# Tiras_LED.net
KiCad netlist of a schematic drawn in Altium Designer
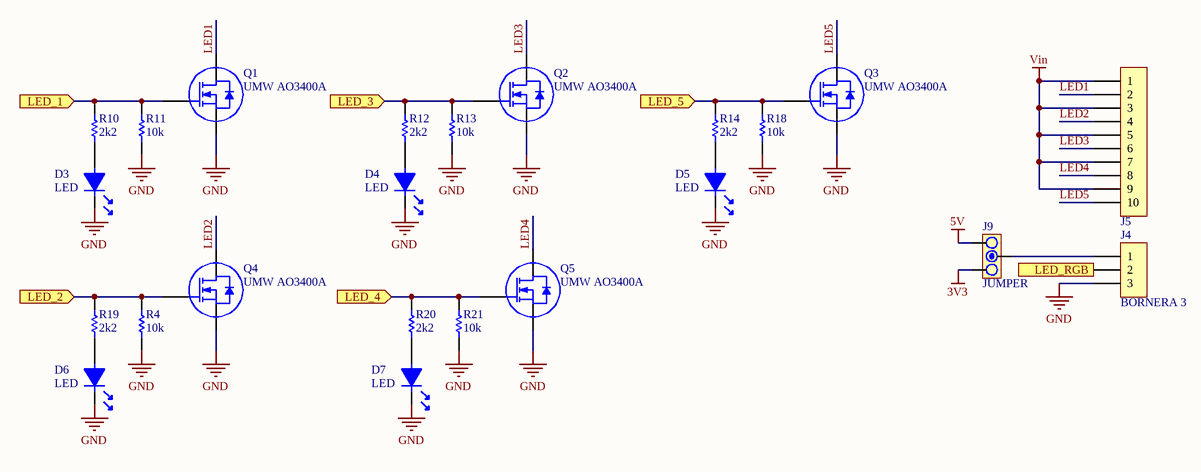
[diagram p0: Tiras LED.SchDoc]

(export (version "E")
  (design (tool "Eeschema 10.0.6"))
  (components
    (comp (ref "D3") (value "LED") (footprint "LED0805") (libsource (lib "LIBPIOIX") (part "LED")))
    (comp (ref "D4") (value "LED") (footprint "LED0805") (libsource (lib "LIBPIOIX") (part "LED")))
    (comp (ref "D5") (value "LED") (footprint "LED0805") (libsource (lib "LIBPIOIX") (part "LED")))
    (comp (ref "D6") (value "LED") (footprint "LED0805") (libsource (lib "LIBPIOIX") (part "LED")))
    (comp (ref "D7") (value "LED") (footprint "LED0805") (libsource (lib "LIBPIOIX") (part "LED")))
    (comp (ref "J4")
      (value "BORNERA 3")
      (footprint "BORNERA3")
      (libsource (lib "LIBPIOIX") (part "BORNERA 3"))
    )
    (comp (ref "J5")
      (value "BORNERA10")
      (footprint "BORNERA10")
      (libsource (lib "LIBPIOIX") (part "BORNERA10"))
    )
    (comp (ref "J9") (value "JUMPER") (footprint "JUMPER3") (libsource (lib "LIBPIOIX") (part "JUMPER3")))
    (comp (ref "Q1") (value "UMW AO3400A") (footprint "SOT23") (libsource (lib "LIBPIOIX") (part "MOSFET N")))
    (comp (ref "Q2") (value "UMW AO3400A") (footprint "SOT23") (libsource (lib "LIBPIOIX") (part "MOSFET N")))
    (comp (ref "Q3") (value "UMW AO3400A") (footprint "SOT23") (libsource (lib "LIBPIOIX") (part "MOSFET N")))
    (comp (ref "Q4") (value "UMW AO3400A") (footprint "SOT23") (libsource (lib "LIBPIOIX") (part "MOSFET N")))
    (comp (ref "Q5") (value "UMW AO3400A") (footprint "SOT23") (libsource (lib "LIBPIOIX") (part "MOSFET N")))
    (comp (ref "R4") (value "10k") (footprint "0805") (libsource (lib "LIBPIOIX") (part "RES")))
    (comp (ref "R10") (value "2k2") (footprint "0805") (libsource (lib "LIBPIOIX") (part "RES")))
    (comp (ref "R11") (value "10k") (footprint "0805") (libsource (lib "LIBPIOIX") (part "RES")))
    (comp (ref "R12") (value "2k2") (footprint "0805") (libsource (lib "LIBPIOIX") (part "RES")))
    (comp (ref "R13") (value "10k") (footprint "0805") (libsource (lib "LIBPIOIX") (part "RES")))
    (comp (ref "R14") (value "2k2") (footprint "0805") (libsource (lib "LIBPIOIX") (part "RES")))
    (comp (ref "R18") (value "10k") (footprint "0805") (libsource (lib "LIBPIOIX") (part "RES")))
    (comp (ref "R19") (value "2k2") (footprint "0805") (libsource (lib "LIBPIOIX") (part "RES")))
    (comp (ref "R20") (value "2k2") (footprint "0805") (libsource (lib "LIBPIOIX") (part "RES")))
    (comp (ref "R21") (value "10k") (footprint "0805") (libsource (lib "LIBPIOIX") (part "RES")))
  )
  (nets
    (net (code "1") (name "/LED1") (class "Default")
      (node (ref "J5") (pin "2") (pinfunction "2_2") (pintype "passive"))
      (node (ref "Q1") (pin "2") (pinfunction "D_2") (pintype "passive"))
    )
    (net (code "2") (name "/LED2") (class "Default")
      (node (ref "J5") (pin "4") (pinfunction "4_4") (pintype "passive"))
      (node (ref "Q4") (pin "2") (pinfunction "D_2") (pintype "passive"))
    )
    (net (code "3") (name "/LED3") (class "Default")
      (node (ref "J5") (pin "6") (pinfunction "6_6") (pintype "passive"))
      (node (ref "Q2") (pin "2") (pinfunction "D_2") (pintype "passive"))
    )
    (net (code "4") (name "/LED4") (class "Default")
      (node (ref "J5") (pin "8") (pinfunction "8_8") (pintype "passive"))
      (node (ref "Q5") (pin "2") (pinfunction "D_2") (pintype "passive"))
    )
    (net (code "5") (name "/LED5") (class "Default")
      (node (ref "J5") (pin "10") (pinfunction "10_10") (pintype "passive"))
      (node (ref "Q3") (pin "2") (pinfunction "D_2") (pintype "passive"))
    )
    (net (code "6") (name "/LED_1") (class "Default")
      (node (ref "Q1") (pin "1") (pinfunction "G_1") (pintype "passive"))
      (node (ref "R10") (pin "2") (pinfunction "2_2") (pintype "passive"))
      (node (ref "R11") (pin "2") (pinfunction "2_2") (pintype "passive"))
    )
    (net (code "7") (name "/LED_2") (class "Default")
      (node (ref "Q4") (pin "1") (pinfunction "G_1") (pintype "passive"))
      (node (ref "R19") (pin "2") (pinfunction "2_2") (pintype "passive"))
      (node (ref "R4") (pin "2") (pinfunction "2_2") (pintype "passive"))
    )
    (net (code "8") (name "/LED_3") (class "Default")
      (node (ref "Q2") (pin "1") (pinfunction "G_1") (pintype "passive"))
      (node (ref "R12") (pin "2") (pinfunction "2_2") (pintype "passive"))
      (node (ref "R13") (pin "2") (pinfunction "2_2") (pintype "passive"))
    )
    (net (code "9") (name "/LED_4") (class "Default")
      (node (ref "Q5") (pin "1") (pinfunction "G_1") (pintype "passive"))
      (node (ref "R20") (pin "2") (pinfunction "2_2") (pintype "passive"))
      (node (ref "R21") (pin "2") (pinfunction "2_2") (pintype "passive"))
    )
    (net (code "10") (name "/LED_5") (class "Default")
      (node (ref "Q3") (pin "1") (pinfunction "G_1") (pintype "passive"))
      (node (ref "R14") (pin "2") (pinfunction "2_2") (pintype "passive"))
      (node (ref "R18") (pin "2") (pinfunction "2_2") (pintype "passive"))
    )
    (net (code "11") (name "/LED_RGB") (class "Default")
      (node (ref "J4") (pin "2") (pinfunction "2_2") (pintype "passive"))
    )
    (net (code "12") (name "3V3") (class "Default")
      (node (ref "J9") (pin "1") (pinfunction "1_1") (pintype "passive"))
    )
    (net (code "13") (name "5V") (class "Default")
      (node (ref "J9") (pin "3") (pinfunction "3_3") (pintype "passive"))
    )
    (net (code "14") (name "GND") (class "Default")
      (node (ref "D3") (pin "2") (pinfunction "2_2") (pintype "passive"))
      (node (ref "D4") (pin "2") (pinfunction "2_2") (pintype "passive"))
      (node (ref "D5") (pin "2") (pinfunction "2_2") (pintype "passive"))
      (node (ref "D6") (pin "2") (pinfunction "2_2") (pintype "passive"))
      (node (ref "D7") (pin "2") (pinfunction "2_2") (pintype "passive"))
      (node (ref "J4") (pin "3") (pinfunction "3_3") (pintype "passive"))
      (node (ref "Q1") (pin "3") (pinfunction "S_3") (pintype "passive"))
      (node (ref "Q2") (pin "3") (pinfunction "S_3") (pintype "passive"))
      (node (ref "Q3") (pin "3") (pinfunction "S_3") (pintype "passive"))
      (node (ref "Q4") (pin "3") (pinfunction "S_3") (pintype "passive"))
      (node (ref "Q5") (pin "3") (pinfunction "S_3") (pintype "passive"))
      (node (ref "R11") (pin "1") (pinfunction "1_1") (pintype "passive"))
      (node (ref "R13") (pin "1") (pinfunction "1_1") (pintype "passive"))
      (node (ref "R18") (pin "1") (pinfunction "1_1") (pintype "passive"))
      (node (ref "R21") (pin "1") (pinfunction "1_1") (pintype "passive"))
      (node (ref "R4") (pin "1") (pinfunction "1_1") (pintype "passive"))
    )
    (net (code "15") (name "Net-(D3-Pad1)") (class "Default")
      (node (ref "D3") (pin "1") (pinfunction "1_1") (pintype "passive"))
      (node (ref "R10") (pin "1") (pinfunction "1_1") (pintype "passive"))
    )
    (net (code "16") (name "Net-(D4-Pad1)") (class "Default")
      (node (ref "D4") (pin "1") (pinfunction "1_1") (pintype "passive"))
      (node (ref "R12") (pin "1") (pinfunction "1_1") (pintype "passive"))
    )
    (net (code "17") (name "Net-(D5-Pad1)") (class "Default")
      (node (ref "D5") (pin "1") (pinfunction "1_1") (pintype "passive"))
      (node (ref "R14") (pin "1") (pinfunction "1_1") (pintype "passive"))
    )
    (net (code "18") (name "Net-(D6-Pad1)") (class "Default")
      (node (ref "D6") (pin "1") (pinfunction "1_1") (pintype "passive"))
      (node (ref "R19") (pin "1") (pinfunction "1_1") (pintype "passive"))
    )
    (net (code "19") (name "Net-(D7-Pad1)") (class "Default")
      (node (ref "D7") (pin "1") (pinfunction "1_1") (pintype "passive"))
      (node (ref "R20") (pin "1") (pinfunction "1_1") (pintype "passive"))
    )
    (net (code "20") (name "Net-(J4-Pad1)") (class "Default")
      (node (ref "J4") (pin "1") (pinfunction "1_1") (pintype "passive"))
      (node (ref "J9") (pin "2") (pinfunction "2_2") (pintype "passive"))
    )
    (net (code "21") (name "Vin") (class "Default")
      (node (ref "J5") (pin "1") (pinfunction "1_1") (pintype "passive"))
      (node (ref "J5") (pin "3") (pinfunction "3_3") (pintype "passive"))
      (node (ref "J5") (pin "5") (pinfunction "5_5") (pintype "passive"))
      (node (ref "J5") (pin "7") (pinfunction "7_7") (pintype "passive"))
      (node (ref "J5") (pin "9") (pinfunction "9_9") (pintype "passive"))
    )
  )
)
